# USB_C.net
KiCad netlist of a schematic drawn in Altium Designer
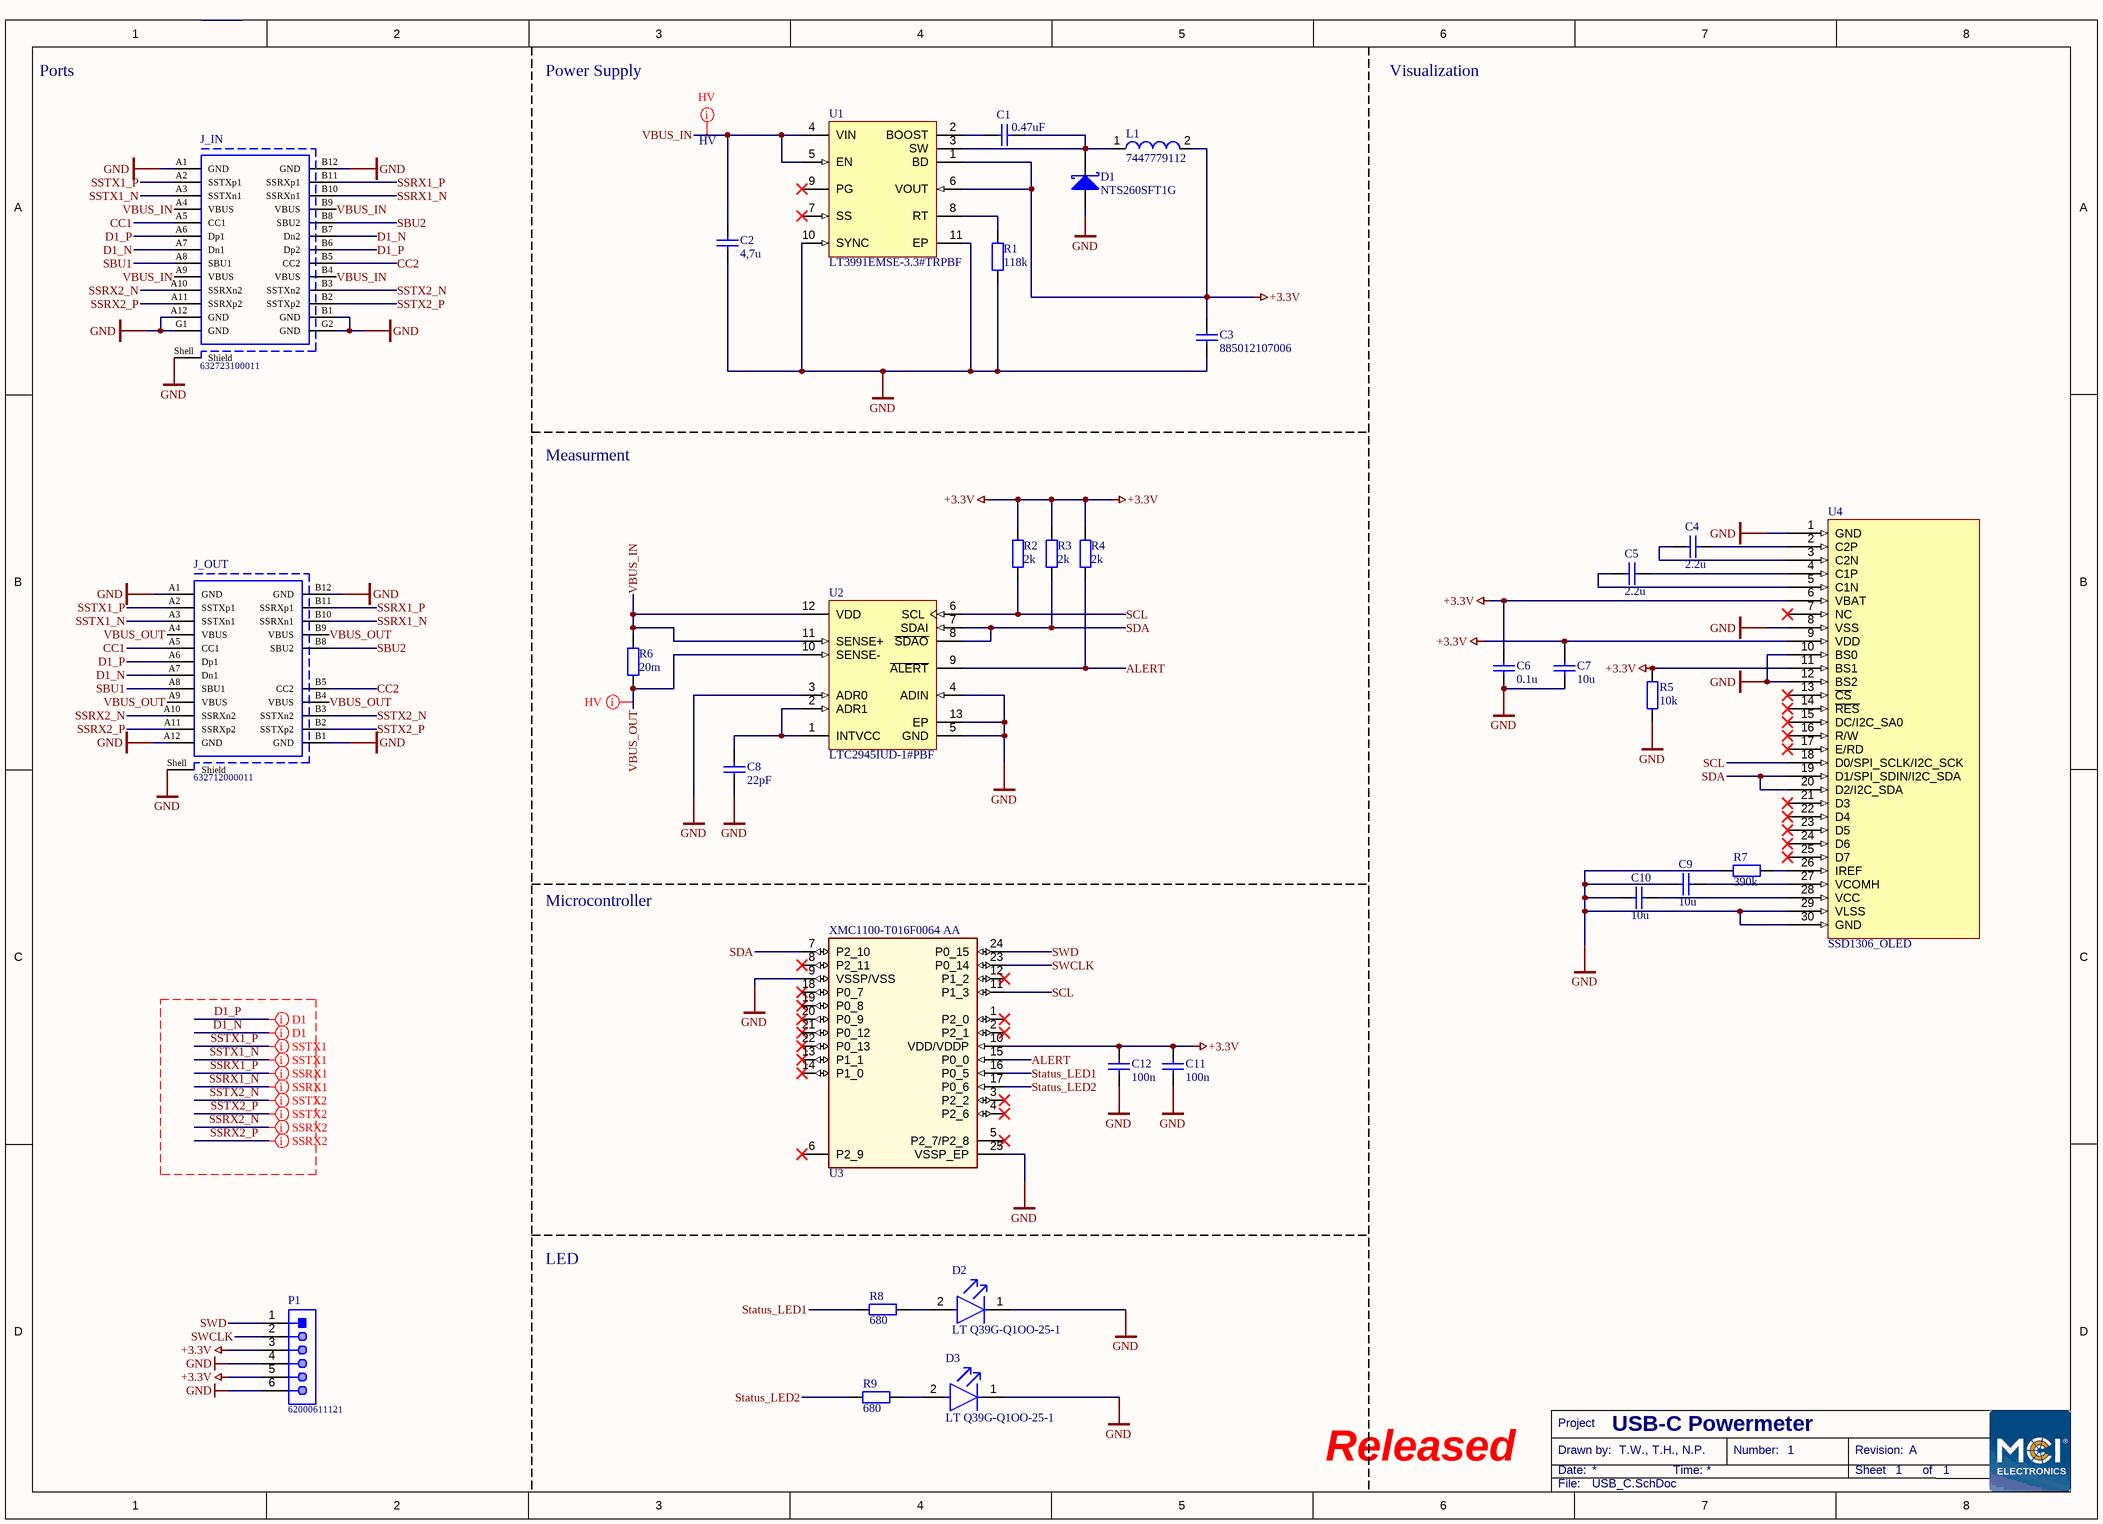
[diagram p0: USB_C.SchDoc]

(export (version "E")
  (design (tool "Eeschema 10.0.6"))
  (components
    (comp (ref "C1") (value "0.47uF") (footprint "_0603") (libsource (lib "Capacitors$") (part "Cap_129")))
    (comp (ref "C2")
      (value "4,7u")
      (footprint "_0805")
      (fields (field (name "VOLTAGE") "50V"))
      (libsource (lib "Capacitors$") (part "Cap_116"))
    )
    (comp (ref "C3")
      (value "885012107006")
      (footprint "_0805")
      (fields (field (name "VOLTAGE") "50V"))
      (libsource (lib "Capacitors$") (part "Cap_111"))
    )
    (comp (ref "C4") (value "2.2u") (footprint "_0603") (libsource (lib "Capacitors$") (part "Cap_129")))
    (comp (ref "C5") (value "2.2u") (footprint "_0603") (libsource (lib "Capacitors$") (part "Cap_129")))
    (comp (ref "C6") (value "0.1u") (footprint "_0603") (libsource (lib "Capacitors$") (part "Cap_129")))
    (comp (ref "C7") (value "10u") (footprint "_0603") (libsource (lib "Capacitors$") (part "Cap_129")))
    (comp (ref "C8") (value "22pF") (footprint "_0603") (libsource (lib "Capacitors$") (part "Cap_129")))
    (comp (ref "C9") (value "10u") (footprint "_0603") (libsource (lib "Capacitors$") (part "Cap_129")))
    (comp (ref "C10") (value "10u") (footprint "_0603") (libsource (lib "Capacitors$") (part "Cap_129")))
    (comp (ref "C11") (value "100n") (footprint "_0603") (libsource (lib "Capacitors$") (part "Cap_129")))
    (comp (ref "C12") (value "100n") (footprint "_0603") (libsource (lib "Capacitors$") (part "Cap_129")))
    (comp (ref "D1") (value "NTS260SFT1G") (footprint "SOD_123") (libsource (lib "Diodes$") (part "DIODE_4")))
    (comp (ref "D2")
      (value "LT Q39G-Q1OO-25-1")
      (footprint "FP-LT_Q39G-MFG")
      (description "LED GREEN DIFFUSED 0603 SMD")
      (libsource (lib "Altium Content Vault") (part "8706943c75ba83719d021d2fdc84c58"))
    )
    (comp (ref "D3")
      (value "LT Q39G-Q1OO-25-1")
      (footprint "FP-LT_Q39G-MFG")
      (description "LED GREEN DIFFUSED 0603 SMD")
      (libsource (lib "Altium Content Vault") (part "8706943c75ba83719d021d2fdc84c58"))
    )
    (comp (ref "J_IN")
      (value "632723100011")
      (footprint "632723100011")
      (description "USB 3.1 Type C Receptacle WR-COM, Horizontal, SMT / THT")
      (fields (field (name "MANUFACTURER") "Wurth Elektronik") (field (name "PUBLISHER") "WurthElektronik"))
      (libsource (lib "Altium Content Vault") (part "WE-632723X00011"))
    )
    (comp (ref "J_OUT")
      (value "632712000011")
      (footprint "632712000011")
      (description "USB 3.1 Type C Plug WR-COM, Horizontal, SMT")
      (fields (field (name "MANUFACTURER") "Wurth Elektronik") (field (name "PUBLISHER") "WurthElektronik"))
      (libsource (lib "Altium Content Vault") (part "WE-632712000011"))
    )
    (comp (ref "L1")
      (value "7447779112")
      (footprint "WE-PD-M-PB")
      (description "SMD-Shielded Power Inductor WE-PD, L = 12.0 µH")
      (libsource (lib "Altium Content Vault") (part "PAS-IND-INDUCTOR-2"))
    )
    (comp (ref "P1")
      (value "62000611121")
      (footprint "62000611121")
      (description "THT Vertical Pin Header WR-PHD, Pitch 2.00 mm, Single Row, 6 pins")
      (fields (field (name "MANUFACTURER") "Wurth Elektronik") (field (name "PUBLISHER") "WurthElektronik"))
      (libsource (lib "Altium Content Vault") (part "WE-CN-1P-M-R6"))
    )
    (comp (ref "R1") (value "118k") (footprint "_0603") (libsource (lib "") (part "Res_5_1")))
    (comp (ref "R2") (value "2k") (footprint "_0603") (libsource (lib "Resistors$") (part "Res_5")))
    (comp (ref "R3") (value "2k") (footprint "_0603") (libsource (lib "Resistors$") (part "Res_5")))
    (comp (ref "R4") (value "2k") (footprint "_0603") (libsource (lib "Resistors$") (part "Res_5")))
    (comp (ref "R5") (value "10k") (footprint "_0603") (libsource (lib "") (part "Res_5_1")))
    (comp (ref "R6") (value "20m") (footprint "_2512") (libsource (lib "Resistors$") (part "Res_11")))
    (comp (ref "R7") (value "390k") (footprint "_0603") (libsource (lib "") (part "Res_5_2")))
    (comp (ref "R8") (value "680") (footprint "_0603") (libsource (lib "") (part "Res_5_2")))
    (comp (ref "R9") (value "680") (footprint "_0603") (libsource (lib "") (part "Res_5_2")))
    (comp (ref "U1")
      (value "LT3991EMSE-3.3#TRPBF")
      (footprint "LT-MSE-10-EDP_N")
      (fields (field (name "MANUFACTURER") "Linear Technology"))
      (libsource (lib "Altium Content Vault") (part "LT-LT3991-MSE-10"))
    )
    (comp (ref "U2")
      (value "LTC2945IUD-1#PBF")
      (footprint "LT-UD-12_L")
      (description "Wide Range I2C Power Monitor, 12-pin QFN (UD-12), -40 to 85 degC, Pb-Free")
      (fields (field (name "MANUFACTURER") "Linear Technology"))
      (libsource (lib "Altium Content Vault") (part "LT-LTC2945-1-UD-12"))
    )
    (comp (ref "U3")
      (value "XMC1100-T016F0064 AA")
      (footprint "QFN50P400X400X90-25N")
      (description "32-bit XMC1000 Industrial Microcontrollers ARM® Cortex™-M0 / PG-VQFN-24-19")
      (fields (field (name "MANUFACTURER") "Infineon") (field (name "PARTNUMBER") "XMC1100-Q024F 0064 AA"))
      (libsource (lib "XMC1100-Q024F0064 AA") (part "XMC1100-Q024F0064 AA"))
    )
    (comp (ref "U4")
      (value "SSD1306_OLED")
      (footprint "SSD1306")
      (libsource (lib "Components") (part "SSD1306_OLED"))
    )
  )
  (nets
    (net (code "1") (name "+3.3V") (class "Default")
      (node (ref "C11") (pin "1") (pinfunction "1_1") (pintype "passive"))
      (node (ref "C12") (pin "1") (pinfunction "1_1") (pintype "passive"))
      (node (ref "C3") (pin "2") (pinfunction "2_2") (pintype "passive"))
      (node (ref "C6") (pin "1") (pinfunction "1_1") (pintype "passive"))
      (node (ref "C7") (pin "1") (pinfunction "1_1") (pintype "passive"))
      (node (ref "L1") (pin "2") (pinfunction "2_2") (pintype "passive"))
      (node (ref "P1") (pin "3") (pinfunction "3_3") (pintype "passive"))
      (node (ref "P1") (pin "5") (pinfunction "5_5") (pintype "passive"))
      (node (ref "R2") (pin "1") (pinfunction "1_1") (pintype "passive"))
      (node (ref "R3") (pin "1") (pinfunction "1_1") (pintype "passive"))
      (node (ref "R4") (pin "1") (pinfunction "1_1") (pintype "passive"))
      (node (ref "R5") (pin "2") (pinfunction "2_2") (pintype "passive"))
      (node (ref "U1") (pin "1") (pinfunction "BD_1") (pintype "power_in"))
      (node (ref "U1") (pin "6") (pinfunction "VOUT_6") (pintype "input"))
      (node (ref "U3") (pin "10") (pinfunction "VDD/VDDP_10") (pintype "input"))
      (node (ref "U4") (pin "11") (pinfunction "BS1_11") (pintype "input"))
      (node (ref "U4") (pin "6") (pinfunction "VBAT_6") (pintype "input"))
      (node (ref "U4") (pin "9") (pinfunction "VDD_9") (pintype "input"))
    )
    (net (code "2") (name "/ALERT") (class "Default")
      (node (ref "R4") (pin "2") (pinfunction "2_2") (pintype "passive"))
      (node (ref "U2") (pin "9") (pinfunction "~{ALERT}_9") (pintype "open_collector"))
      (node (ref "U3") (pin "15") (pinfunction "P0_0_15") (pintype "input"))
    )
    (net (code "3") (name "/CC1") (class "Default")
      (node (ref "J_IN") (pin "A5") (pinfunction "CC1_A5") (pintype "passive"))
      (node (ref "J_OUT") (pin "A5") (pinfunction "CC1_A5") (pintype "passive"))
    )
    (net (code "4") (name "/CC2") (class "Default")
      (node (ref "J_IN") (pin "B5") (pinfunction "CC2_B5") (pintype "passive"))
      (node (ref "J_OUT") (pin "B5") (pinfunction "CC2_B5") (pintype "passive"))
    )
    (net (code "5") (name "/D1_N") (class "Default")
      (node (ref "J_IN") (pin "A7") (pinfunction "Dn1_A7") (pintype "passive"))
      (node (ref "J_IN") (pin "B7") (pinfunction "Dn2_B7") (pintype "passive"))
      (node (ref "J_OUT") (pin "A7") (pinfunction "Dn1_A7") (pintype "passive"))
    )
    (net (code "6") (name "/D1_P") (class "Default")
      (node (ref "J_IN") (pin "A6") (pinfunction "Dp1_A6") (pintype "passive"))
      (node (ref "J_IN") (pin "B6") (pinfunction "Dp2_B6") (pintype "passive"))
      (node (ref "J_OUT") (pin "A6") (pinfunction "Dp1_A6") (pintype "passive"))
    )
    (net (code "7") (name "/SBU1") (class "Default")
      (node (ref "J_IN") (pin "A8") (pinfunction "SBU1_A8") (pintype "passive"))
      (node (ref "J_OUT") (pin "A8") (pinfunction "SBU1_A8") (pintype "passive"))
    )
    (net (code "8") (name "/SBU2") (class "Default")
      (node (ref "J_IN") (pin "B8") (pinfunction "SBU2_B8") (pintype "passive"))
      (node (ref "J_OUT") (pin "B8") (pinfunction "SBU2_B8") (pintype "passive"))
    )
    (net (code "9") (name "/SCL") (class "Default")
      (node (ref "R2") (pin "2") (pinfunction "2_2") (pintype "passive"))
      (node (ref "U2") (pin "6") (pinfunction "SCL_6") (pintype "input"))
      (node (ref "U3") (pin "11") (pinfunction "P1_3_11") (pintype "bidirectional"))
      (node (ref "U4") (pin "18") (pinfunction "D0/SPI_SCLK/I2C_SCK_18") (pintype "input"))
    )
    (net (code "10") (name "/SDA") (class "Default")
      (node (ref "R3") (pin "2") (pinfunction "2_2") (pintype "passive"))
      (node (ref "U2") (pin "7") (pinfunction "SDAI_7") (pintype "input"))
      (node (ref "U2") (pin "8") (pinfunction "~{SDAO}_8") (pintype "open_collector"))
      (node (ref "U3") (pin "7") (pinfunction "P2_10_7") (pintype "bidirectional"))
      (node (ref "U4") (pin "19") (pinfunction "D1/SPI_SDIN/I2C_SDA_19") (pintype "input"))
      (node (ref "U4") (pin "20") (pinfunction "D2/I2C_SDA_20") (pintype "input"))
    )
    (net (code "11") (name "/SSRX1_N") (class "Default")
      (node (ref "J_IN") (pin "B10") (pinfunction "SSRXn1_B10") (pintype "passive"))
      (node (ref "J_OUT") (pin "B10") (pinfunction "SSRXn1_B10") (pintype "passive"))
    )
    (net (code "12") (name "/SSRX1_P") (class "Default")
      (node (ref "J_IN") (pin "B11") (pinfunction "SSRXp1_B11") (pintype "passive"))
      (node (ref "J_OUT") (pin "B11") (pinfunction "SSRXp1_B11") (pintype "passive"))
    )
    (net (code "13") (name "/SSRX2_N") (class "Default")
      (node (ref "J_IN") (pin "A10") (pinfunction "SSRXn2_A10") (pintype "passive"))
      (node (ref "J_OUT") (pin "A10") (pinfunction "SSRXn2_A10") (pintype "passive"))
    )
    (net (code "14") (name "/SSRX2_P") (class "Default")
      (node (ref "J_IN") (pin "A11") (pinfunction "SSRXp2_A11") (pintype "passive"))
      (node (ref "J_OUT") (pin "A11") (pinfunction "SSRXp2_A11") (pintype "passive"))
    )
    (net (code "15") (name "/SSTX1_N") (class "Default")
      (node (ref "J_IN") (pin "A3") (pinfunction "SSTXn1_A3") (pintype "passive"))
      (node (ref "J_OUT") (pin "A3") (pinfunction "SSTXn1_A3") (pintype "passive"))
    )
    (net (code "16") (name "/SSTX1_P") (class "Default")
      (node (ref "J_IN") (pin "A2") (pinfunction "SSTXp1_A2") (pintype "passive"))
      (node (ref "J_OUT") (pin "A2") (pinfunction "SSTXp1_A2") (pintype "passive"))
    )
    (net (code "17") (name "/SSTX2_N") (class "Default")
      (node (ref "J_IN") (pin "B3") (pinfunction "SSTXn2_B3") (pintype "passive"))
      (node (ref "J_OUT") (pin "B3") (pinfunction "SSTXn2_B3") (pintype "passive"))
    )
    (net (code "18") (name "/SSTX2_P") (class "Default")
      (node (ref "J_IN") (pin "B2") (pinfunction "SSTXp2_B2") (pintype "passive"))
      (node (ref "J_OUT") (pin "B2") (pinfunction "SSTXp2_B2") (pintype "passive"))
    )
    (net (code "19") (name "/SWCLK") (class "Default")
      (node (ref "P1") (pin "2") (pinfunction "2_2") (pintype "passive"))
      (node (ref "U3") (pin "23") (pinfunction "P0_14_23") (pintype "bidirectional"))
    )
    (net (code "20") (name "/SWD") (class "Default")
      (node (ref "P1") (pin "1") (pinfunction "1_1") (pintype "passive"))
      (node (ref "U3") (pin "24") (pinfunction "P0_15_24") (pintype "bidirectional"))
    )
    (net (code "21") (name "/Status_LED1") (class "Default")
      (node (ref "R8") (pin "2") (pinfunction "2_2") (pintype "passive"))
      (node (ref "U3") (pin "16") (pinfunction "P0_5_16") (pintype "input"))
    )
    (net (code "22") (name "/Status_LED2") (class "Default")
      (node (ref "R9") (pin "2") (pinfunction "2_2") (pintype "passive"))
      (node (ref "U3") (pin "17") (pinfunction "P0_6_17") (pintype "input"))
    )
    (net (code "23") (name "/VBUS_IN") (class "Default")
      (node (ref "C2") (pin "2") (pinfunction "2_2") (pintype "passive"))
      (node (ref "J_IN") (pin "A4") (pinfunction "VBUS_A4") (pintype "passive"))
      (node (ref "J_IN") (pin "A9") (pinfunction "VBUS_A9") (pintype "passive"))
      (node (ref "J_IN") (pin "B4") (pinfunction "VBUS_B4") (pintype "passive"))
      (node (ref "J_IN") (pin "B9") (pinfunction "VBUS_B9") (pintype "passive"))
      (node (ref "R6") (pin "1") (pinfunction "1_1") (pintype "passive"))
      (node (ref "U1") (pin "4") (pinfunction "VIN_4") (pintype "power_in"))
      (node (ref "U1") (pin "5") (pinfunction "EN_5") (pintype "input"))
      (node (ref "U2") (pin "11") (pinfunction "SENSE+_11") (pintype "input"))
      (node (ref "U2") (pin "12") (pinfunction "VDD_12") (pintype "power_in"))
    )
    (net (code "24") (name "/VBUS_OUT") (class "Default")
      (node (ref "J_OUT") (pin "A4") (pinfunction "VBUS_A4") (pintype "passive"))
      (node (ref "J_OUT") (pin "A9") (pinfunction "VBUS_A9") (pintype "passive"))
      (node (ref "J_OUT") (pin "B4") (pinfunction "VBUS_B4") (pintype "passive"))
      (node (ref "J_OUT") (pin "B9") (pinfunction "VBUS_B9") (pintype "passive"))
      (node (ref "R6") (pin "2") (pinfunction "2_2") (pintype "passive"))
      (node (ref "U2") (pin "10") (pinfunction "SENSE-_10") (pintype "input"))
    )
    (net (code "25") (name "GND") (class "Default")
      (node (ref "C10") (pin "2") (pinfunction "2_2") (pintype "passive"))
      (node (ref "C11") (pin "2") (pinfunction "2_2") (pintype "passive"))
      (node (ref "C12") (pin "2") (pinfunction "2_2") (pintype "passive"))
      (node (ref "C2") (pin "1") (pinfunction "1_1") (pintype "passive"))
      (node (ref "C3") (pin "1") (pinfunction "1_1") (pintype "passive"))
      (node (ref "C6") (pin "2") (pinfunction "2_2") (pintype "passive"))
      (node (ref "C7") (pin "2") (pinfunction "2_2") (pintype "passive"))
      (node (ref "C8") (pin "1") (pinfunction "1_1") (pintype "passive"))
      (node (ref "C9") (pin "2") (pinfunction "2_2") (pintype "passive"))
      (node (ref "D1") (pin "1") (pinfunction "A_1") (pintype "passive"))
      (node (ref "D2") (pin "1") (pinfunction "C_1") (pintype "passive"))
      (node (ref "D3") (pin "1") (pinfunction "C_1") (pintype "passive"))
      (node (ref "J_IN") (pin "A1") (pinfunction "GND_A1") (pintype "passive"))
      (node (ref "J_IN") (pin "A12") (pinfunction "GND_A12") (pintype "passive"))
      (node (ref "J_IN") (pin "B1") (pinfunction "GND_B1") (pintype "passive"))
      (node (ref "J_IN") (pin "B12") (pinfunction "GND_B12") (pintype "passive"))
      (node (ref "J_IN") (pin "G1") (pinfunction "GND_G1") (pintype "passive"))
      (node (ref "J_IN") (pin "G2") (pinfunction "GND_G2") (pintype "passive"))
      (node (ref "J_IN") (pin "Shell") (pinfunction "Shield_Shell") (pintype "passive"))
      (node (ref "J_OUT") (pin "A1") (pinfunction "GND_A1") (pintype "passive"))
      (node (ref "J_OUT") (pin "A12") (pinfunction "GND_A12") (pintype "passive"))
      (node (ref "J_OUT") (pin "B1") (pinfunction "GND_B1") (pintype "passive"))
      (node (ref "J_OUT") (pin "B12") (pinfunction "GND_B12") (pintype "passive"))
      (node (ref "J_OUT") (pin "Shell") (pinfunction "Shield_Shell") (pintype "passive"))
      (node (ref "P1") (pin "4") (pinfunction "4_4") (pintype "passive"))
      (node (ref "P1") (pin "6") (pinfunction "6_6") (pintype "passive"))
      (node (ref "R1") (pin "1") (pinfunction "1_1") (pintype "passive"))
      (node (ref "R5") (pin "1") (pinfunction "1_1") (pintype "passive"))
      (node (ref "R7") (pin "2") (pinfunction "2_2") (pintype "passive"))
      (node (ref "U1") (pin "10") (pinfunction "SYNC_10") (pintype "input"))
      (node (ref "U1") (pin "11") (pinfunction "EP_11") (pintype "power_in"))
      (node (ref "U2") (pin "13") (pinfunction "EP_13") (pintype "power_in"))
      (node (ref "U2") (pin "3") (pinfunction "ADR0_3") (pintype "input"))
      (node (ref "U2") (pin "4") (pinfunction "ADIN_4") (pintype "input"))
      (node (ref "U2") (pin "5") (pinfunction "GND_5") (pintype "power_in"))
      (node (ref "U3") (pin "25") (pinfunction "VSSP_EP_25") (pintype "power_in"))
      (node (ref "U3") (pin "9") (pinfunction "VSSP/VSS_9") (pintype "bidirectional"))
      (node (ref "U4") (pin "1") (pinfunction "GND_1") (pintype "input"))
      (node (ref "U4") (pin "10") (pinfunction "BS0_10") (pintype "input"))
      (node (ref "U4") (pin "12") (pinfunction "BS2_12") (pintype "input"))
      (node (ref "U4") (pin "29") (pinfunction "VLSS_29") (pintype "input"))
      (node (ref "U4") (pin "30") (pinfunction "GND_30") (pintype "input"))
      (node (ref "U4") (pin "8") (pinfunction "VSS_8") (pintype "input"))
    )
    (net (code "26") (name "Net-(D1-K)") (class "Default")
      (node (ref "C1") (pin "1") (pinfunction "1_1") (pintype "passive"))
      (node (ref "D1") (pin "2") (pinfunction "K_2") (pintype "passive"))
      (node (ref "L1") (pin "1") (pinfunction "1_1") (pintype "passive"))
      (node (ref "U1") (pin "3") (pinfunction "SW_3") (pintype "power_in"))
    )
    (net (code "27") (name "Net-(D2-A)") (class "Default")
      (node (ref "D2") (pin "2") (pinfunction "A_2") (pintype "passive"))
      (node (ref "R8") (pin "1") (pinfunction "1_1") (pintype "passive"))
    )
    (net (code "28") (name "Net-(D3-A)") (class "Default")
      (node (ref "D3") (pin "2") (pinfunction "A_2") (pintype "passive"))
      (node (ref "R9") (pin "1") (pinfunction "1_1") (pintype "passive"))
    )
    (net (code "29") (name "Net-(U1-BOOST)") (class "Default")
      (node (ref "C1") (pin "2") (pinfunction "2_2") (pintype "passive"))
      (node (ref "U1") (pin "2") (pinfunction "BOOST_2") (pintype "passive"))
    )
    (net (code "30") (name "Net-(U1-RT)") (class "Default")
      (node (ref "R1") (pin "2") (pinfunction "2_2") (pintype "passive"))
      (node (ref "U1") (pin "8") (pinfunction "RT_8") (pintype "passive"))
    )
    (net (code "31") (name "Net-(U2-ADR1)") (class "Default")
      (node (ref "C8") (pin "2") (pinfunction "2_2") (pintype "passive"))
      (node (ref "U2") (pin "1") (pinfunction "INTVCC_1") (pintype "power_in"))
      (node (ref "U2") (pin "2") (pinfunction "ADR1_2") (pintype "input"))
    )
    (net (code "32") (name "Net-(U4-C1N)") (class "Default")
      (node (ref "C5") (pin "2") (pinfunction "2_2") (pintype "passive"))
      (node (ref "U4") (pin "5") (pinfunction "C1N_5") (pintype "input"))
    )
    (net (code "33") (name "Net-(U4-C1P)") (class "Default")
      (node (ref "C5") (pin "1") (pinfunction "1_1") (pintype "passive"))
      (node (ref "U4") (pin "4") (pinfunction "C1P_4") (pintype "input"))
    )
    (net (code "34") (name "Net-(U4-C2N)") (class "Default")
      (node (ref "C4") (pin "2") (pinfunction "2_2") (pintype "passive"))
      (node (ref "U4") (pin "3") (pinfunction "C2N_3") (pintype "input"))
    )
    (net (code "35") (name "Net-(U4-C2P)") (class "Default")
      (node (ref "C4") (pin "1") (pinfunction "1_1") (pintype "passive"))
      (node (ref "U4") (pin "2") (pinfunction "C2P_2") (pintype "input"))
    )
    (net (code "36") (name "Net-(U4-IREF)") (class "Default")
      (node (ref "R7") (pin "1") (pinfunction "1_1") (pintype "passive"))
      (node (ref "U4") (pin "26") (pinfunction "IREF_26") (pintype "input"))
    )
    (net (code "37") (name "Net-(U4-VCC)") (class "Default")
      (node (ref "C10") (pin "1") (pinfunction "1_1") (pintype "passive"))
      (node (ref "U4") (pin "28") (pinfunction "VCC_28") (pintype "input"))
    )
    (net (code "38") (name "Net-(U4-VCOMH)") (class "Default")
      (node (ref "C9") (pin "1") (pinfunction "1_1") (pintype "passive"))
      (node (ref "U4") (pin "27") (pinfunction "VCOMH_27") (pintype "input"))
    )
    (net (code "39") (name "unconnected-(U1-PG-Pad9)") (class "Default")
      (node (ref "U1") (pin "9") (pinfunction "PG_9") (pintype "open_collector+no_connect"))
    )
    (net (code "40") (name "unconnected-(U1-SS-Pad7)") (class "Default")
      (node (ref "U1") (pin "7") (pinfunction "SS_7") (pintype "input+no_connect"))
    )
    (net (code "41") (name "unconnected-(U3-P0_7-Pad18)") (class "Default")
      (node (ref "U3") (pin "18") (pinfunction "P0_7_18") (pintype "bidirectional+no_connect"))
    )
    (net (code "42") (name "unconnected-(U3-P0_8-Pad19)") (class "Default")
      (node (ref "U3") (pin "19") (pinfunction "P0_8_19") (pintype "bidirectional+no_connect"))
    )
    (net (code "43") (name "unconnected-(U3-P0_9-Pad20)") (class "Default")
      (node (ref "U3") (pin "20") (pinfunction "P0_9_20") (pintype "bidirectional+no_connect"))
    )
    (net (code "44") (name "unconnected-(U3-P0_12-Pad21)") (class "Default")
      (node (ref "U3") (pin "21") (pinfunction "P0_12_21") (pintype "bidirectional+no_connect"))
    )
    (net (code "45") (name "unconnected-(U3-P0_13-Pad22)") (class "Default")
      (node (ref "U3") (pin "22") (pinfunction "P0_13_22") (pintype "bidirectional+no_connect"))
    )
    (net (code "46") (name "unconnected-(U3-P1_0-Pad14)") (class "Default")
      (node (ref "U3") (pin "14") (pinfunction "P1_0_14") (pintype "bidirectional+no_connect"))
    )
    (net (code "47") (name "unconnected-(U3-P1_1-Pad13)") (class "Default")
      (node (ref "U3") (pin "13") (pinfunction "P1_1_13") (pintype "bidirectional+no_connect"))
    )
    (net (code "48") (name "unconnected-(U3-P1_2-Pad12)") (class "Default")
      (node (ref "U3") (pin "12") (pinfunction "P1_2_12") (pintype "bidirectional+no_connect"))
    )
    (net (code "49") (name "unconnected-(U3-P2_0-Pad1)") (class "Default")
      (node (ref "U3") (pin "1") (pinfunction "P2_0_1") (pintype "bidirectional+no_connect"))
    )
    (net (code "50") (name "unconnected-(U3-P2_1-Pad2)") (class "Default")
      (node (ref "U3") (pin "2") (pinfunction "P2_1_2") (pintype "bidirectional+no_connect"))
    )
    (net (code "51") (name "unconnected-(U3-P2_2-Pad3)") (class "Default")
      (node (ref "U3") (pin "3") (pinfunction "P2_2_3") (pintype "bidirectional+no_connect"))
    )
    (net (code "52") (name "unconnected-(U3-P2_6-Pad4)") (class "Default")
      (node (ref "U3") (pin "4") (pinfunction "P2_6_4") (pintype "bidirectional+no_connect"))
    )
    (net (code "53") (name "unconnected-(U3-P2_7{slash}P2_8-Pad5)") (class "Default")
      (node (ref "U3") (pin "5") (pinfunction "P2_7/P2_8_5") (pintype "power_in+no_connect"))
    )
    (net (code "54") (name "unconnected-(U3-P2_9-Pad6)") (class "Default")
      (node (ref "U3") (pin "6") (pinfunction "P2_9_6") (pintype "power_in+no_connect"))
    )
    (net (code "55") (name "unconnected-(U3-P2_11-Pad8)") (class "Default")
      (node (ref "U3") (pin "8") (pinfunction "P2_11_8") (pintype "bidirectional+no_connect"))
    )
    (net (code "56") (name "unconnected-(U4-CS-Pad13)") (class "Default")
      (node (ref "U4") (pin "13") (pinfunction "CS_13") (pintype "input+no_connect"))
    )
    (net (code "57") (name "unconnected-(U4-D3-Pad21)") (class "Default")
      (node (ref "U4") (pin "21") (pinfunction "D3_21") (pintype "input+no_connect"))
    )
    (net (code "58") (name "unconnected-(U4-D4-Pad22)") (class "Default")
      (node (ref "U4") (pin "22") (pinfunction "D4_22") (pintype "input+no_connect"))
    )
    (net (code "59") (name "unconnected-(U4-D5-Pad23)") (class "Default")
      (node (ref "U4") (pin "23") (pinfunction "D5_23") (pintype "input+no_connect"))
    )
    (net (code "60") (name "unconnected-(U4-D6-Pad24)") (class "Default")
      (node (ref "U4") (pin "24") (pinfunction "D6_24") (pintype "input+no_connect"))
    )
    (net (code "61") (name "unconnected-(U4-D7-Pad25)") (class "Default")
      (node (ref "U4") (pin "25") (pinfunction "D7_25") (pintype "input+no_connect"))
    )
    (net (code "62") (name "unconnected-(U4-DC{slash}I2C_SA0-Pad15)") (class "Default")
      (node (ref "U4") (pin "15") (pinfunction "DC/I2C_SA0_15") (pintype "input+no_connect"))
    )
    (net (code "63") (name "unconnected-(U4-E{slash}RD-Pad17)") (class "Default")
      (node (ref "U4") (pin "17") (pinfunction "E/RD_17") (pintype "input+no_connect"))
    )
    (net (code "64") (name "unconnected-(U4-NC-Pad7)") (class "Default")
      (node (ref "U4") (pin "7") (pinfunction "NC_7") (pintype "input+no_connect"))
    )
    (net (code "65") (name "unconnected-(U4-RES-Pad14)") (class "Default")
      (node (ref "U4") (pin "14") (pinfunction "RES_14") (pintype "input+no_connect"))
    )
    (net (code "66") (name "unconnected-(U4-R{slash}W-Pad16)") (class "Default")
      (node (ref "U4") (pin "16") (pinfunction "R/W_16") (pintype "input+no_connect"))
    )
  )
)
